# rs485.net
KiCad netlist of a schematic drawn in Altium Designer
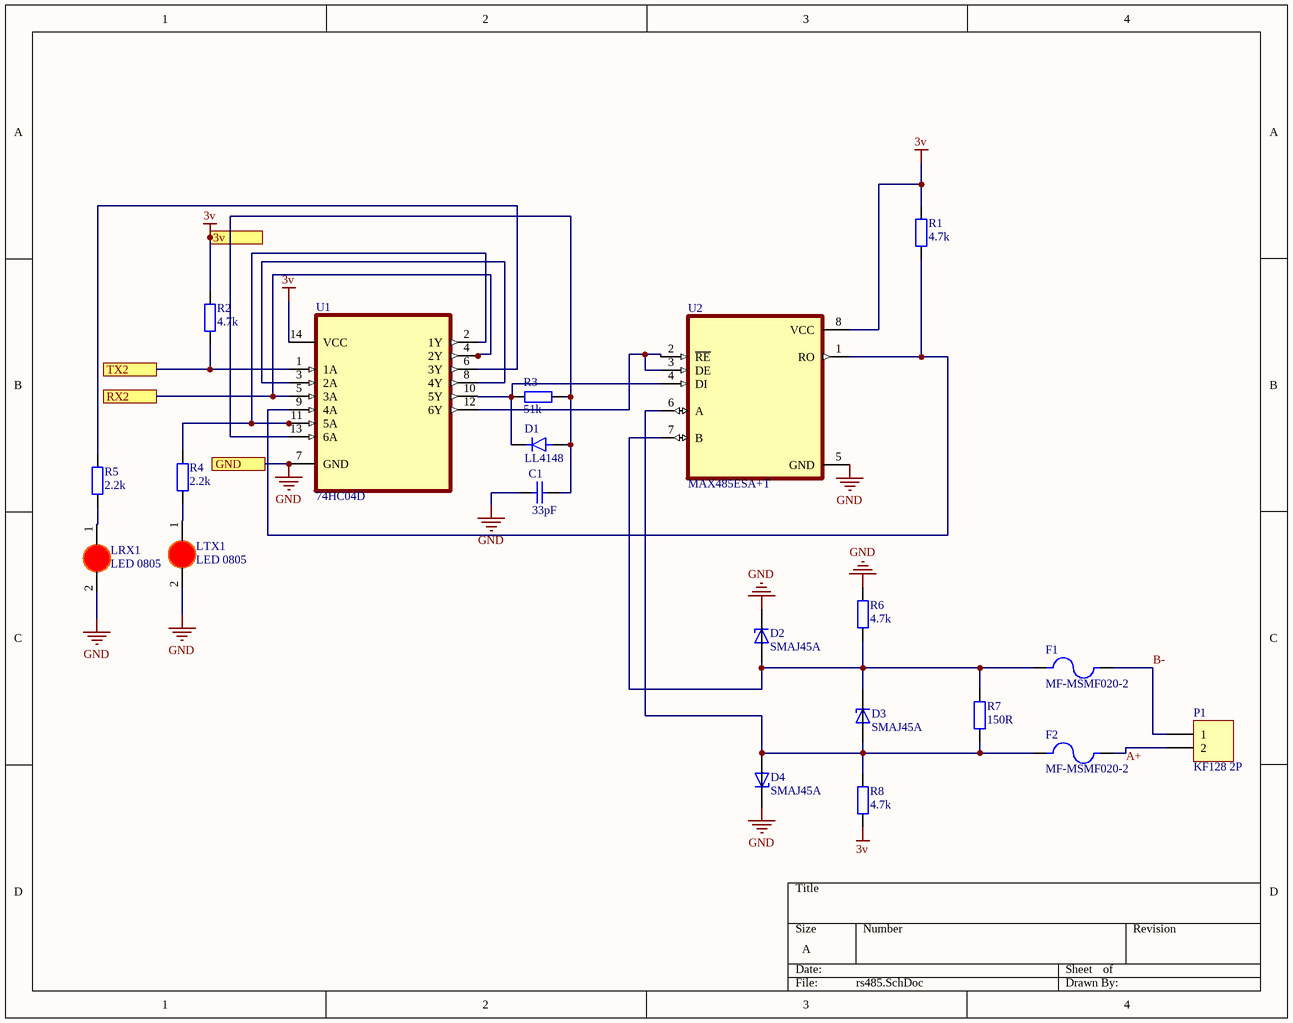
[diagram p0: rs485.SchDoc]

(export (version "E")
  (design (tool "Eeschema 10.0.6"))
  (components
    (comp (ref "C1")
      (value "33pF")
      (footprint "tu 0805")
      (description "Dán")
      (libsource (lib "Altium_Lib_by_KhueNguyenCreator") (part "Tu 0805 33pF 50V 10%"))
    )
    (comp (ref "D1")
      (value "LL4148")
      (footprint "DIO_LL4148")
      (description "Diode Small Signal Switching 100V 0.15A Automotive 2-Pin Mini-MELF T/R")
      (fields (field (name "MF") "Diotec Semiconductor"))
      (libsource (lib "LinhKienDoAn") (part "LL4148"))
    )
    (comp (ref "D2")
      (value "SMAJ45A")
      (footprint "DIOM4325X250N")
      (description "72.7V Clamp 5.5A Ipp Tvs Diode Surface Mount DO-214AC (SMA)")
      (fields (field (name "MF") "Littelfuse"))
      (libsource (lib "LinhKienDoAn") (part "SMAJ45A"))
    )
    (comp (ref "D3")
      (value "SMAJ45A")
      (footprint "DIOM4325X250N")
      (description "72.7V Clamp 5.5A Ipp Tvs Diode Surface Mount DO-214AC (SMA)")
      (fields (field (name "MF") "Littelfuse"))
      (libsource (lib "LinhKienDoAn") (part "SMAJ45A"))
    )
    (comp (ref "D4")
      (value "SMAJ45A")
      (footprint "DIOM4325X250N")
      (description "72.7V Clamp 5.5A Ipp Tvs Diode Surface Mount DO-214AC (SMA)")
      (fields (field (name "MF") "Littelfuse"))
      (libsource (lib "LinhKienDoAn") (part "SMAJ45A"))
    )
    (comp (ref "F1")
      (value "MF-MSMF020-2")
      (footprint "FUSER_MF-MSMF020-2")
      (description "Polymeric PTC Resettable Fuse 30V 200 mA Ih Surface Mount 1812 (4532 Metric), Concave")
      (fields (field (name "MF") "Bourns"))
      (libsource (lib "LinhKienDoAn") (part "MF-MSMF020-2"))
    )
    (comp (ref "F2")
      (value "MF-MSMF020-2")
      (footprint "FUSER_MF-MSMF020-2")
      (description "Polymeric PTC Resettable Fuse 30V 200 mA Ih Surface Mount 1812 (4532 Metric), Concave")
      (fields (field (name "MF") "Bourns"))
      (libsource (lib "LinhKienDoAn") (part "MF-MSMF020-2"))
    )
    (comp (ref "LRX1")
      (value "LED 0805")
      (footprint "LED-0805-Red")
      (description "Dán")
      (libsource (lib "Altium_Lib_by_KhueNguyenCreator") (part "LED 0805 Do"))
    )
    (comp (ref "LTX1")
      (value "LED 0805")
      (footprint "LED-0805-Red")
      (description "Dán")
      (libsource (lib "Altium_Lib_by_KhueNguyenCreator") (part "LED 0805 Do"))
    )
    (comp (ref "P1")
      (value "KF128 2P")
      (footprint "KF128_2P")
      (description "Header, 2-Pin, pitch 5.08mm")
      (fields (field (name "MPN") "KF128-2P"))
      (libsource (lib "BYTECH_HW_LIB_2019 (1)") (part "KF128 2P"))
    )
    (comp (ref "R1")
      (value "4.7k")
      (footprint "tro smd 0603")
      (description "Dán")
      (libsource (lib "Altium_Lib_by_KhueNguyenCreator") (part "Tro 0603 5% 4.7k"))
    )
    (comp (ref "R2")
      (value "4.7k")
      (footprint "tro smd 0603")
      (description "Dán")
      (libsource (lib "Altium_Lib_by_KhueNguyenCreator") (part "Tro 0603 5% 4.7k"))
    )
    (comp (ref "R3")
      (value "51k")
      (footprint "tro smd 0603")
      (description "Dán")
      (libsource (lib "Altium_Lib_by_KhueNguyenCreator") (part "Tro 0603 5% 51k"))
    )
    (comp (ref "R4")
      (value "2.2k")
      (footprint "tro smd 0603")
      (description "Dán")
      (libsource (lib "Altium_Lib_by_KhueNguyenCreator") (part "Tro 0603 5% 2.2k"))
    )
    (comp (ref "R5")
      (value "2.2k")
      (footprint "tro smd 0603")
      (description "Dán")
      (libsource (lib "Altium_Lib_by_KhueNguyenCreator") (part "Tro 0603 5% 2.2k"))
    )
    (comp (ref "R6")
      (value "4.7k")
      (footprint "tro smd 0603")
      (description "Dán")
      (libsource (lib "Altium_Lib_by_KhueNguyenCreator") (part "Tro 0603 5% 4.7k"))
    )
    (comp (ref "R7")
      (value "150R")
      (footprint "tro smd 0603")
      (description "Dán")
      (libsource (lib "Altium_Lib_by_KhueNguyenCreator") (part "Tro 0603 5% 150R"))
    )
    (comp (ref "R8")
      (value "4.7k")
      (footprint "tro smd 0603")
      (description "Dán")
      (libsource (lib "Altium_Lib_by_KhueNguyenCreator") (part "Tro 0603 5% 4.7k"))
    )
    (comp (ref "U1")
      (value "74HC04D")
      (footprint "SOIC127P600X175-14N")
      (description "Inverter IC 6 Channel 14-SOIC")
      (fields (field (name "MF") "Toshiba"))
      (libsource (lib "LinhKienDoAn") (part "74HC04D"))
    )
    (comp (ref "U2")
      (value "MAX485ESA+T")
      (footprint "SOIC127P600X175-8N")
      (description "1/1 Transceiver Half RS422, RS485 8-SOIC")
      (fields (field (name "MP") "MAX485ESA") (field (name "MF") "Maxim Integrated"))
      (libsource (lib "MAX485ESA_T") (part "MAX485ESA+T"))
    )
  )
  (nets
    (net (code "1") (name "/A+") (class "Default")
      (node (ref "F2") (pin "2") (pinfunction "2_2") (pintype "passive"))
      (node (ref "P1") (pin "2") (pinfunction "2_2") (pintype "passive"))
    )
    (net (code "2") (name "/B-") (class "Default")
      (node (ref "F1") (pin "2") (pinfunction "2_2") (pintype "passive"))
      (node (ref "P1") (pin "1") (pinfunction "1_1") (pintype "passive"))
    )
    (net (code "3") (name "/RX2") (class "Default")
      (node (ref "U1") (pin "4") (pinfunction "2Y_4") (pintype "output"))
      (node (ref "U1") (pin "5") (pinfunction "3A_5") (pintype "input"))
    )
    (net (code "4") (name "/TX2") (class "Default")
      (node (ref "R2") (pin "1") (pinfunction "1_1") (pintype "passive"))
      (node (ref "U1") (pin "1") (pinfunction "1A_1") (pintype "input"))
    )
    (net (code "5") (name "3v") (class "Default")
      (node (ref "R1") (pin "2") (pinfunction "2_2") (pintype "passive"))
      (node (ref "R2") (pin "2") (pinfunction "2_2") (pintype "passive"))
      (node (ref "R8") (pin "1") (pinfunction "1_1") (pintype "passive"))
      (node (ref "U1") (pin "14") (pinfunction "VCC_14") (pintype "power_in"))
      (node (ref "U2") (pin "8") (pinfunction "VCC_8") (pintype "power_in"))
    )
    (net (code "6") (name "GND") (class "Default")
      (node (ref "C1") (pin "2") (pinfunction "2_2") (pintype "passive"))
      (node (ref "D2") (pin "C") (pinfunction "C_C") (pintype "passive"))
      (node (ref "D4") (pin "C") (pinfunction "C_C") (pintype "passive"))
      (node (ref "LRX1") (pin "2") (pinfunction "K_2") (pintype "passive"))
      (node (ref "LTX1") (pin "2") (pinfunction "K_2") (pintype "passive"))
      (node (ref "R6") (pin "2") (pinfunction "2_2") (pintype "passive"))
      (node (ref "U1") (pin "7") (pinfunction "GND_7") (pintype "passive"))
      (node (ref "U2") (pin "5") (pinfunction "GND_5") (pintype "power_in"))
    )
    (net (code "7") (name "Net-(LRX1-A)") (class "Default")
      (node (ref "LRX1") (pin "1") (pinfunction "A_1") (pintype "passive"))
      (node (ref "R5") (pin "1") (pinfunction "1_1") (pintype "passive"))
    )
    (net (code "8") (name "Net-(LTX1-A)") (class "Default")
      (node (ref "LTX1") (pin "1") (pinfunction "A_1") (pintype "passive"))
      (node (ref "R4") (pin "1") (pinfunction "1_1") (pintype "passive"))
    )
    (net (code "9") (name "Net-(U1-1Y)") (class "Default")
      (node (ref "R4") (pin "2") (pinfunction "2_2") (pintype "passive"))
      (node (ref "U1") (pin "11") (pinfunction "5A_11") (pintype "input"))
      (node (ref "U1") (pin "2") (pinfunction "1Y_2") (pintype "output"))
    )
    (net (code "10") (name "Net-(U1-2A)") (class "Default")
      (node (ref "U1") (pin "3") (pinfunction "2A_3") (pintype "input"))
      (node (ref "U1") (pin "8") (pinfunction "4Y_8") (pintype "output"))
    )
    (net (code "11") (name "Net-(U1-3Y)") (class "Default")
      (node (ref "R5") (pin "2") (pinfunction "2_2") (pintype "passive"))
      (node (ref "U1") (pin "6") (pinfunction "3Y_6") (pintype "output"))
    )
    (net (code "12") (name "Net-(U1-4A)") (class "Default")
      (node (ref "R1") (pin "1") (pinfunction "1_1") (pintype "passive"))
      (node (ref "U1") (pin "9") (pinfunction "4A_9") (pintype "input"))
      (node (ref "U2") (pin "1") (pinfunction "RO_1") (pintype "output"))
    )
    (net (code "13") (name "Net-(U1-5Y)") (class "Default")
      (node (ref "D1") (pin "C") (pinfunction "C_C") (pintype "passive"))
      (node (ref "R3") (pin "1") (pinfunction "1_1") (pintype "passive"))
      (node (ref "U1") (pin "10") (pinfunction "5Y_10") (pintype "output"))
      (node (ref "U2") (pin "4") (pinfunction "DI_4") (pintype "input"))
    )
    (net (code "14") (name "Net-(U1-6A)") (class "Default")
      (node (ref "C1") (pin "1") (pinfunction "1_1") (pintype "passive"))
      (node (ref "D1") (pin "A") (pinfunction "A_A") (pintype "passive"))
      (node (ref "R3") (pin "2") (pinfunction "2_2") (pintype "passive"))
      (node (ref "U1") (pin "13") (pinfunction "6A_13") (pintype "input"))
    )
    (net (code "15") (name "Net-(U1-6Y)") (class "Default")
      (node (ref "U1") (pin "12") (pinfunction "6Y_12") (pintype "output"))
      (node (ref "U2") (pin "2") (pinfunction "~{RE}_2") (pintype "input"))
      (node (ref "U2") (pin "3") (pinfunction "DE_3") (pintype "input"))
    )
    (net (code "16") (name "Net-(U2-A)") (class "Default")
      (node (ref "D3") (pin "A") (pinfunction "A_A") (pintype "passive"))
      (node (ref "D4") (pin "A") (pinfunction "A_A") (pintype "passive"))
      (node (ref "F2") (pin "1") (pinfunction "1_1") (pintype "passive"))
      (node (ref "R7") (pin "1") (pinfunction "1_1") (pintype "passive"))
      (node (ref "R8") (pin "2") (pinfunction "2_2") (pintype "passive"))
      (node (ref "U2") (pin "6") (pinfunction "A_6") (pintype "bidirectional"))
    )
    (net (code "17") (name "Net-(U2-B)") (class "Default")
      (node (ref "D2") (pin "A") (pinfunction "A_A") (pintype "passive"))
      (node (ref "D3") (pin "C") (pinfunction "C_C") (pintype "passive"))
      (node (ref "F1") (pin "1") (pinfunction "1_1") (pintype "passive"))
      (node (ref "R6") (pin "1") (pinfunction "1_1") (pintype "passive"))
      (node (ref "R7") (pin "2") (pinfunction "2_2") (pintype "passive"))
      (node (ref "U2") (pin "7") (pinfunction "B_7") (pintype "bidirectional"))
    )
  )
)
